# Arduino.net
KiCad netlist of a schematic drawn in Altium Designer
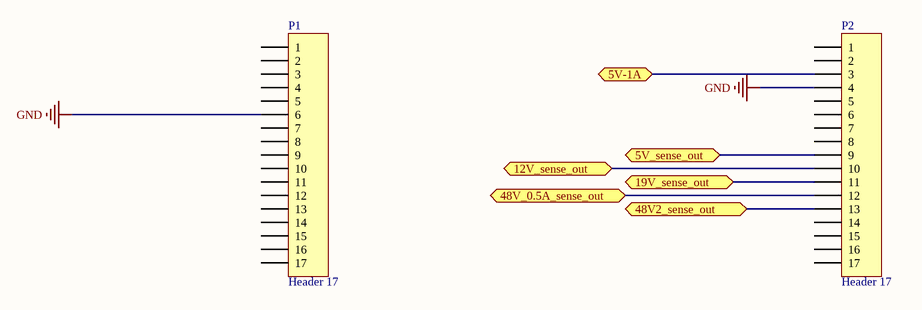
[diagram p0: Arduino.SchDoc]

(export (version "E")
  (design (tool "Eeschema 10.0.6"))
  (components
    (comp (ref "P1")
      (value "Header 17")
      (footprint "HDR1X17")
      (description "Header, 17-Pin")
      (fields (field (name "PUBLISHER") "Altium Limited"))
      (libsource (lib "Miscellaneous Connectors") (part "Header 17"))
    )
    (comp (ref "P2")
      (value "Header 17")
      (footprint "HDR1X17")
      (description "Header, 17-Pin")
      (fields (field (name "PUBLISHER") "Altium Limited"))
      (libsource (lib "Miscellaneous Connectors") (part "Header 17"))
    )
  )
  (nets
    (net (code "1") (name "/5V-1A") (class "Default")
      (node (ref "P2") (pin "3") (pinfunction "3_3") (pintype "passive"))
    )
    (net (code "2") (name "/5V_sense_out") (class "Default")
      (node (ref "P2") (pin "9") (pinfunction "9_9") (pintype "passive"))
    )
    (net (code "3") (name "/12V_sense_out") (class "Default")
      (node (ref "P2") (pin "10") (pinfunction "10_10") (pintype "passive"))
    )
    (net (code "4") (name "/19V_sense_out") (class "Default")
      (node (ref "P2") (pin "11") (pinfunction "11_11") (pintype "passive"))
    )
    (net (code "5") (name "/48V2_sense_out") (class "Default")
      (node (ref "P2") (pin "13") (pinfunction "13_13") (pintype "passive"))
    )
    (net (code "6") (name "/48V_0.5A_sense_out") (class "Default")
      (node (ref "P2") (pin "12") (pinfunction "12_12") (pintype "passive"))
    )
    (net (code "7") (name "GND") (class "Default")
      (node (ref "P1") (pin "6") (pinfunction "6_6") (pintype "passive"))
      (node (ref "P2") (pin "4") (pinfunction "4_4") (pintype "passive"))
    )
    (net (code "8") (name "unconnected-(P1-Pad1)") (class "Default")
      (node (ref "P1") (pin "1") (pinfunction "1_1") (pintype "passive"))
    )
    (net (code "9") (name "unconnected-(P1-Pad2)") (class "Default")
      (node (ref "P1") (pin "2") (pinfunction "2_2") (pintype "passive"))
    )
    (net (code "10") (name "unconnected-(P1-Pad3)") (class "Default")
      (node (ref "P1") (pin "3") (pinfunction "3_3") (pintype "passive"))
    )
    (net (code "11") (name "unconnected-(P1-Pad4)") (class "Default")
      (node (ref "P1") (pin "4") (pinfunction "4_4") (pintype "passive"))
    )
    (net (code "12") (name "unconnected-(P1-Pad5)") (class "Default")
      (node (ref "P1") (pin "5") (pinfunction "5_5") (pintype "passive"))
    )
    (net (code "13") (name "unconnected-(P1-Pad7)") (class "Default")
      (node (ref "P1") (pin "7") (pinfunction "7_7") (pintype "passive"))
    )
    (net (code "14") (name "unconnected-(P1-Pad8)") (class "Default")
      (node (ref "P1") (pin "8") (pinfunction "8_8") (pintype "passive"))
    )
    (net (code "15") (name "unconnected-(P1-Pad9)") (class "Default")
      (node (ref "P1") (pin "9") (pinfunction "9_9") (pintype "passive"))
    )
    (net (code "16") (name "unconnected-(P1-Pad10)") (class "Default")
      (node (ref "P1") (pin "10") (pinfunction "10_10") (pintype "passive"))
    )
    (net (code "17") (name "unconnected-(P1-Pad11)") (class "Default")
      (node (ref "P1") (pin "11") (pinfunction "11_11") (pintype "passive"))
    )
    (net (code "18") (name "unconnected-(P1-Pad12)") (class "Default")
      (node (ref "P1") (pin "12") (pinfunction "12_12") (pintype "passive"))
    )
    (net (code "19") (name "unconnected-(P1-Pad13)") (class "Default")
      (node (ref "P1") (pin "13") (pinfunction "13_13") (pintype "passive"))
    )
    (net (code "20") (name "unconnected-(P1-Pad14)") (class "Default")
      (node (ref "P1") (pin "14") (pinfunction "14_14") (pintype "passive"))
    )
    (net (code "21") (name "unconnected-(P1-Pad15)") (class "Default")
      (node (ref "P1") (pin "15") (pinfunction "15_15") (pintype "passive"))
    )
    (net (code "22") (name "unconnected-(P1-Pad16)") (class "Default")
      (node (ref "P1") (pin "16") (pinfunction "16_16") (pintype "passive"))
    )
    (net (code "23") (name "unconnected-(P1-Pad17)") (class "Default")
      (node (ref "P1") (pin "17") (pinfunction "17_17") (pintype "passive"))
    )
    (net (code "24") (name "unconnected-(P2-Pad1)") (class "Default")
      (node (ref "P2") (pin "1") (pinfunction "1_1") (pintype "passive"))
    )
    (net (code "25") (name "unconnected-(P2-Pad2)") (class "Default")
      (node (ref "P2") (pin "2") (pinfunction "2_2") (pintype "passive"))
    )
    (net (code "26") (name "unconnected-(P2-Pad5)") (class "Default")
      (node (ref "P2") (pin "5") (pinfunction "5_5") (pintype "passive"))
    )
    (net (code "27") (name "unconnected-(P2-Pad6)") (class "Default")
      (node (ref "P2") (pin "6") (pinfunction "6_6") (pintype "passive"))
    )
    (net (code "28") (name "unconnected-(P2-Pad7)") (class "Default")
      (node (ref "P2") (pin "7") (pinfunction "7_7") (pintype "passive"))
    )
    (net (code "29") (name "unconnected-(P2-Pad8)") (class "Default")
      (node (ref "P2") (pin "8") (pinfunction "8_8") (pintype "passive"))
    )
    (net (code "30") (name "unconnected-(P2-Pad14)") (class "Default")
      (node (ref "P2") (pin "14") (pinfunction "14_14") (pintype "passive"))
    )
    (net (code "31") (name "unconnected-(P2-Pad15)") (class "Default")
      (node (ref "P2") (pin "15") (pinfunction "15_15") (pintype "passive"))
    )
    (net (code "32") (name "unconnected-(P2-Pad16)") (class "Default")
      (node (ref "P2") (pin "16") (pinfunction "16_16") (pintype "passive"))
    )
    (net (code "33") (name "unconnected-(P2-Pad17)") (class "Default")
      (node (ref "P2") (pin "17") (pinfunction "17_17") (pintype "passive"))
    )
  )
)
